# LED.net
KiCad netlist of a schematic drawn in EAGLE
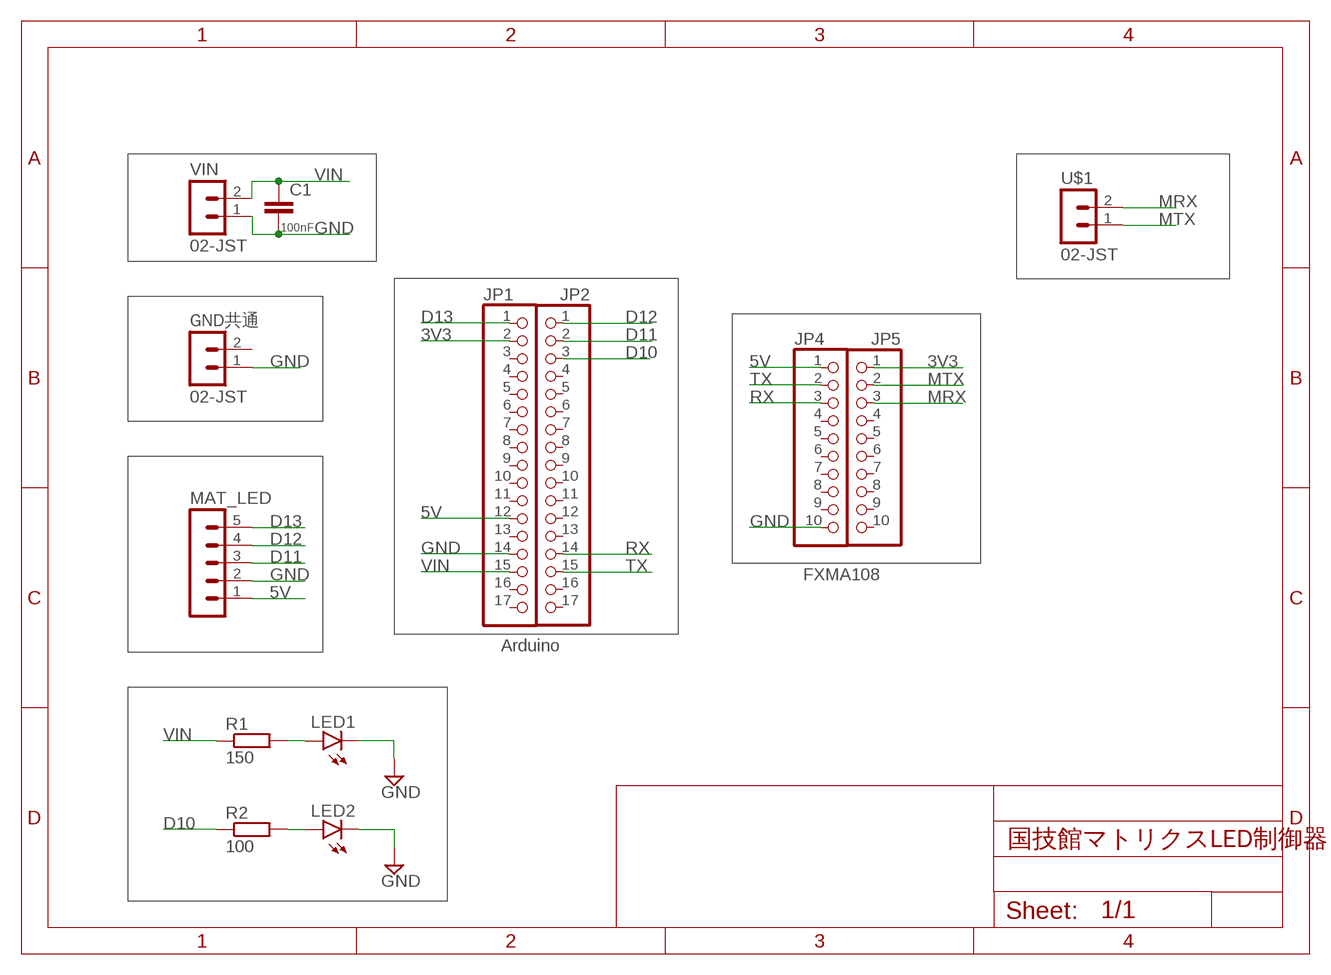
[diagram p0: schematic, sheet 1]

(export (version "E")
  (design (tool "Eeschema 10.0.6"))
  (components
    (comp (ref "C1")
      (value "100nF")
      (footprint "eagle-import:C025-024X044")
      (libsource (lib "eagle-import") (part "C-EU025-024X044"))
    )
    (comp (ref "GND共通")
      (value "02-JST")
      (footprint "eagle-import:B2B-XH")
      (libsource (lib "eagle-import") (part "02-JST"))
    )
    (comp (ref "JP1")
      (value "PINHD-1X17")
      (footprint "eagle-import:1X17")
      (libsource (lib "eagle-import") (part "PINHD-1X17"))
    )
    (comp (ref "JP2")
      (value "PINHD-1X17")
      (footprint "eagle-import:1X17")
      (libsource (lib "eagle-import") (part "PINHD-1X17"))
    )
    (comp (ref "JP4")
      (value "PINHD-1X10")
      (footprint "eagle-import:1X10")
      (libsource (lib "eagle-import") (part "PINHD-1X10"))
    )
    (comp (ref "JP5")
      (value "PINHD-1X10")
      (footprint "eagle-import:1X10")
      (libsource (lib "eagle-import") (part "PINHD-1X10"))
    )
    (comp (ref "LED1")
      (value "LED3MM")
      (footprint "eagle-import:LED3MM")
      (libsource (lib "eagle-import") (part "LED3MM"))
    )
    (comp (ref "LED2")
      (value "LED3MM")
      (footprint "eagle-import:LED3MM")
      (libsource (lib "eagle-import") (part "LED3MM"))
    )
    (comp (ref "MAT_LED")
      (value "05-JST")
      (footprint "eagle-import:B5B-XH")
      (libsource (lib "eagle-import") (part "05-JST"))
    )
    (comp (ref "R1")
      (value "150")
      (footprint "eagle-import:0204_7")
      (libsource (lib "eagle-import") (part "R-EU_0204/7"))
    )
    (comp (ref "R2")
      (value "100")
      (footprint "eagle-import:0204_7")
      (libsource (lib "eagle-import") (part "R-EU_0204/7"))
    )
    (comp (ref "U$1")
      (value "02-JST")
      (footprint "eagle-import:B2B-XH")
      (libsource (lib "eagle-import") (part "02-JST"))
    )
    (comp (ref "VIN")
      (value "02-JST")
      (footprint "eagle-import:B2B-XH")
      (libsource (lib "eagle-import") (part "02-JST"))
    )
  )
  (nets
    (net (code "1") (name "/3V3") (class "Default")
      (node (ref "JP1") (pin "2") (pinfunction "2_2") (pintype "passive"))
      (node (ref "JP5") (pin "1") (pinfunction "1_1") (pintype "passive"))
    )
    (net (code "2") (name "/5V") (class "Default")
      (node (ref "JP1") (pin "12") (pinfunction "12_12") (pintype "passive"))
      (node (ref "JP4") (pin "1") (pinfunction "1_1") (pintype "passive"))
      (node (ref "MAT_LED") (pin "1") (pinfunction "1_1") (pintype "passive"))
    )
    (net (code "3") (name "/D10") (class "Default")
      (node (ref "JP2") (pin "3") (pinfunction "3_3") (pintype "passive"))
      (node (ref "R2") (pin "1") (pinfunction "1_1") (pintype "passive"))
    )
    (net (code "4") (name "/D11") (class "Default")
      (node (ref "JP2") (pin "2") (pinfunction "2_2") (pintype "passive"))
      (node (ref "MAT_LED") (pin "3") (pinfunction "3_3") (pintype "passive"))
    )
    (net (code "5") (name "/D12") (class "Default")
      (node (ref "JP2") (pin "1") (pinfunction "1_1") (pintype "passive"))
      (node (ref "MAT_LED") (pin "4") (pinfunction "4_4") (pintype "passive"))
    )
    (net (code "6") (name "/D13") (class "Default")
      (node (ref "JP1") (pin "1") (pinfunction "1_1") (pintype "passive"))
      (node (ref "MAT_LED") (pin "5") (pinfunction "5_5") (pintype "passive"))
    )
    (net (code "7") (name "/MRX") (class "Default")
      (node (ref "JP5") (pin "3") (pinfunction "3_3") (pintype "passive"))
      (node (ref "U$1") (pin "2") (pinfunction "2_2") (pintype "passive"))
    )
    (net (code "8") (name "/MTX") (class "Default")
      (node (ref "JP5") (pin "2") (pinfunction "2_2") (pintype "passive"))
      (node (ref "U$1") (pin "1") (pinfunction "1_1") (pintype "passive"))
    )
    (net (code "9") (name "/RX") (class "Default")
      (node (ref "JP2") (pin "14") (pinfunction "14_14") (pintype "passive"))
      (node (ref "JP4") (pin "3") (pinfunction "3_3") (pintype "passive"))
    )
    (net (code "10") (name "/TX") (class "Default")
      (node (ref "JP2") (pin "15") (pinfunction "15_15") (pintype "passive"))
      (node (ref "JP4") (pin "2") (pinfunction "2_2") (pintype "passive"))
    )
    (net (code "11") (name "/VIN") (class "Default")
      (node (ref "C1") (pin "1") (pinfunction "1_1") (pintype "passive"))
      (node (ref "JP1") (pin "15") (pinfunction "15_15") (pintype "passive"))
      (node (ref "R1") (pin "1") (pinfunction "1_1") (pintype "passive"))
      (node (ref "VIN") (pin "2") (pinfunction "2_2") (pintype "passive"))
    )
    (net (code "12") (name "GND") (class "Default")
      (node (ref "C1") (pin "2") (pinfunction "2_2") (pintype "passive"))
      (node (ref "GND共通") (pin "1") (pinfunction "1_1") (pintype "passive"))
      (node (ref "JP1") (pin "14") (pinfunction "14_14") (pintype "passive"))
      (node (ref "JP4") (pin "10") (pinfunction "10_10") (pintype "passive"))
      (node (ref "LED1") (pin "K") (pinfunction "C_K") (pintype "passive"))
      (node (ref "LED2") (pin "K") (pinfunction "C_K") (pintype "passive"))
      (node (ref "MAT_LED") (pin "2") (pinfunction "2_2") (pintype "passive"))
      (node (ref "VIN") (pin "1") (pinfunction "1_1") (pintype "passive"))
    )
    (net (code "13") (name "Net-(LED1-PadA)") (class "Default")
      (node (ref "LED1") (pin "A") (pinfunction "A_A") (pintype "passive"))
      (node (ref "R1") (pin "2") (pinfunction "2_2") (pintype "passive"))
    )
    (net (code "14") (name "Net-(LED2-PadA)") (class "Default")
      (node (ref "LED2") (pin "A") (pinfunction "A_A") (pintype "passive"))
      (node (ref "R2") (pin "2") (pinfunction "2_2") (pintype "passive"))
    )
    (net (code "15") (name "unconnected-(GND共通-Pad2)") (class "Default")
      (node (ref "GND共通") (pin "2") (pinfunction "2_2") (pintype "passive"))
    )
    (net (code "16") (name "unconnected-(JP1-Pad3)") (class "Default")
      (node (ref "JP1") (pin "3") (pinfunction "3_3") (pintype "passive"))
    )
    (net (code "17") (name "unconnected-(JP1-Pad4)") (class "Default")
      (node (ref "JP1") (pin "4") (pinfunction "4_4") (pintype "passive"))
    )
    (net (code "18") (name "unconnected-(JP1-Pad5)") (class "Default")
      (node (ref "JP1") (pin "5") (pinfunction "5_5") (pintype "passive"))
    )
    (net (code "19") (name "unconnected-(JP1-Pad6)") (class "Default")
      (node (ref "JP1") (pin "6") (pinfunction "6_6") (pintype "passive"))
    )
    (net (code "20") (name "unconnected-(JP1-Pad7)") (class "Default")
      (node (ref "JP1") (pin "7") (pinfunction "7_7") (pintype "passive"))
    )
    (net (code "21") (name "unconnected-(JP1-Pad8)") (class "Default")
      (node (ref "JP1") (pin "8") (pinfunction "8_8") (pintype "passive"))
    )
    (net (code "22") (name "unconnected-(JP1-Pad9)") (class "Default")
      (node (ref "JP1") (pin "9") (pinfunction "9_9") (pintype "passive"))
    )
    (net (code "23") (name "unconnected-(JP1-Pad10)") (class "Default")
      (node (ref "JP1") (pin "10") (pinfunction "10_10") (pintype "passive"))
    )
    (net (code "24") (name "unconnected-(JP1-Pad11)") (class "Default")
      (node (ref "JP1") (pin "11") (pinfunction "11_11") (pintype "passive"))
    )
    (net (code "25") (name "unconnected-(JP1-Pad13)") (class "Default")
      (node (ref "JP1") (pin "13") (pinfunction "13_13") (pintype "passive"))
    )
    (net (code "26") (name "unconnected-(JP1-Pad16)") (class "Default")
      (node (ref "JP1") (pin "16") (pinfunction "16_16") (pintype "passive"))
    )
    (net (code "27") (name "unconnected-(JP1-Pad17)") (class "Default")
      (node (ref "JP1") (pin "17") (pinfunction "17_17") (pintype "passive"))
    )
    (net (code "28") (name "unconnected-(JP2-Pad4)") (class "Default")
      (node (ref "JP2") (pin "4") (pinfunction "4_4") (pintype "passive"))
    )
    (net (code "29") (name "unconnected-(JP2-Pad5)") (class "Default")
      (node (ref "JP2") (pin "5") (pinfunction "5_5") (pintype "passive"))
    )
    (net (code "30") (name "unconnected-(JP2-Pad6)") (class "Default")
      (node (ref "JP2") (pin "6") (pinfunction "6_6") (pintype "passive"))
    )
    (net (code "31") (name "unconnected-(JP2-Pad7)") (class "Default")
      (node (ref "JP2") (pin "7") (pinfunction "7_7") (pintype "passive"))
    )
    (net (code "32") (name "unconnected-(JP2-Pad8)") (class "Default")
      (node (ref "JP2") (pin "8") (pinfunction "8_8") (pintype "passive"))
    )
    (net (code "33") (name "unconnected-(JP2-Pad9)") (class "Default")
      (node (ref "JP2") (pin "9") (pinfunction "9_9") (pintype "passive"))
    )
    (net (code "34") (name "unconnected-(JP2-Pad10)") (class "Default")
      (node (ref "JP2") (pin "10") (pinfunction "10_10") (pintype "passive"))
    )
    (net (code "35") (name "unconnected-(JP2-Pad11)") (class "Default")
      (node (ref "JP2") (pin "11") (pinfunction "11_11") (pintype "passive"))
    )
    (net (code "36") (name "unconnected-(JP2-Pad12)") (class "Default")
      (node (ref "JP2") (pin "12") (pinfunction "12_12") (pintype "passive"))
    )
    (net (code "37") (name "unconnected-(JP2-Pad13)") (class "Default")
      (node (ref "JP2") (pin "13") (pinfunction "13_13") (pintype "passive"))
    )
    (net (code "38") (name "unconnected-(JP2-Pad16)") (class "Default")
      (node (ref "JP2") (pin "16") (pinfunction "16_16") (pintype "passive"))
    )
    (net (code "39") (name "unconnected-(JP2-Pad17)") (class "Default")
      (node (ref "JP2") (pin "17") (pinfunction "17_17") (pintype "passive"))
    )
    (net (code "40") (name "unconnected-(JP4-Pad4)") (class "Default")
      (node (ref "JP4") (pin "4") (pinfunction "4_4") (pintype "passive"))
    )
    (net (code "41") (name "unconnected-(JP4-Pad5)") (class "Default")
      (node (ref "JP4") (pin "5") (pinfunction "5_5") (pintype "passive"))
    )
    (net (code "42") (name "unconnected-(JP4-Pad6)") (class "Default")
      (node (ref "JP4") (pin "6") (pinfunction "6_6") (pintype "passive"))
    )
    (net (code "43") (name "unconnected-(JP4-Pad7)") (class "Default")
      (node (ref "JP4") (pin "7") (pinfunction "7_7") (pintype "passive"))
    )
    (net (code "44") (name "unconnected-(JP4-Pad8)") (class "Default")
      (node (ref "JP4") (pin "8") (pinfunction "8_8") (pintype "passive"))
    )
    (net (code "45") (name "unconnected-(JP4-Pad9)") (class "Default")
      (node (ref "JP4") (pin "9") (pinfunction "9_9") (pintype "passive"))
    )
    (net (code "46") (name "unconnected-(JP5-Pad4)") (class "Default")
      (node (ref "JP5") (pin "4") (pinfunction "4_4") (pintype "passive"))
    )
    (net (code "47") (name "unconnected-(JP5-Pad5)") (class "Default")
      (node (ref "JP5") (pin "5") (pinfunction "5_5") (pintype "passive"))
    )
    (net (code "48") (name "unconnected-(JP5-Pad6)") (class "Default")
      (node (ref "JP5") (pin "6") (pinfunction "6_6") (pintype "passive"))
    )
    (net (code "49") (name "unconnected-(JP5-Pad7)") (class "Default")
      (node (ref "JP5") (pin "7") (pinfunction "7_7") (pintype "passive"))
    )
    (net (code "50") (name "unconnected-(JP5-Pad8)") (class "Default")
      (node (ref "JP5") (pin "8") (pinfunction "8_8") (pintype "passive"))
    )
    (net (code "51") (name "unconnected-(JP5-Pad9)") (class "Default")
      (node (ref "JP5") (pin "9") (pinfunction "9_9") (pintype "passive"))
    )
    (net (code "52") (name "unconnected-(JP5-Pad10)") (class "Default")
      (node (ref "JP5") (pin "10") (pinfunction "10_10") (pintype "passive"))
    )
  )
)
